# Sch_USBSerie.net
KiCad netlist of a schematic drawn in Altium Designer
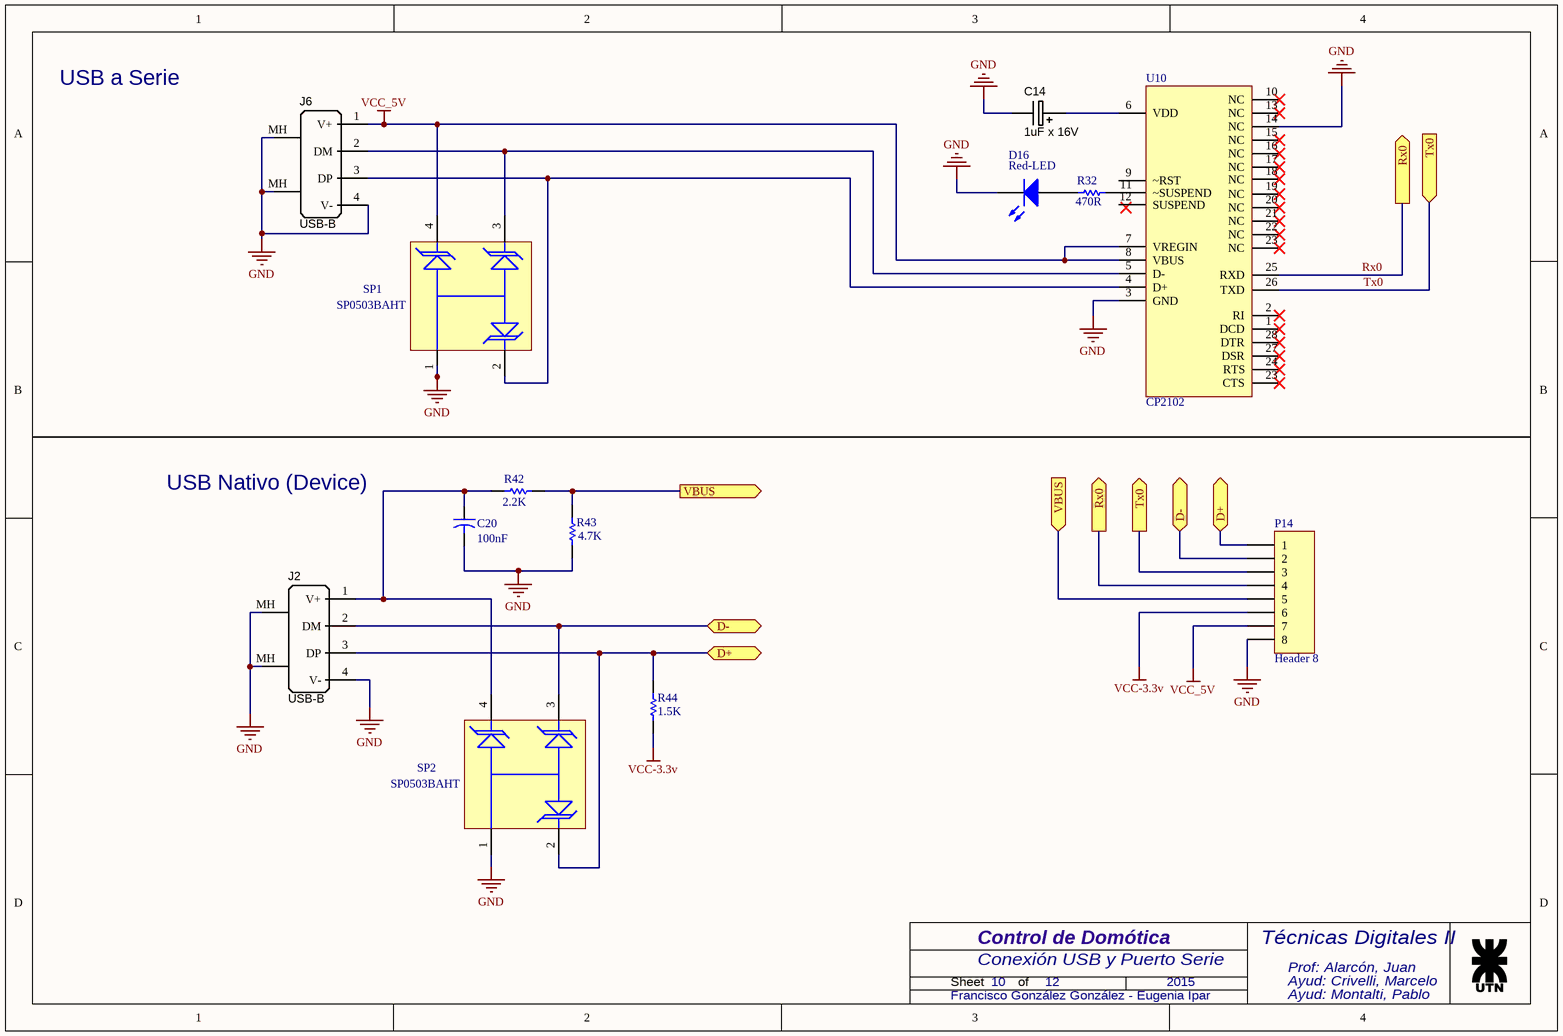
[diagram p0: Sch_USBSerie.SchDoc]

(export (version "E")
  (design (tool "Eeschema 10.0.6"))
  (components
    (comp (ref "C14")
      (value "1uF x 16V")
      (footprint "CAPE3.5mm")
      (description "Capacitor THT Alum Elec 220uF 20% 16V")
      (fields (field (name "TOLERANCE") "±20%"))
      (libsource (lib "PBL - Capacitors") (part "CAPE_220u_16V_THD"))
    )
    (comp (ref "C20")
      (value "100nF")
      (footprint "CAPR5-4X5")
      (description "Capacitor")
      (fields (field (name "Comment") "Cap2") (field (name "PUBLISHER") "Altium Limited"))
      (libsource (lib "Miscellaneous Devices") (part "Cap2"))
    )
    (comp (ref "D16")
      (value "Red-LED")
      (footprint "Type 3mm")
      (description "THT LED round mono-color color lens, WL-TMRW, Super Red")
      (fields (field (name "PARTNUMBER") "151031SS06000") (field (name "MANUFACTURER") "Wuerth Elektronik"))
      (libsource (lib "Altium Content Vault") (part "WE-LED_K1A2-2"))
    )
    (comp (ref "J2")
      (value "USB-B")
      (footprint "USB_TypeB_Tyco")
      (description "Connector THT Type B USB connector")
      (libsource (lib "PBL - Connectors") (part "USB_TypeB"))
    )
    (comp (ref "J6")
      (value "USB-B")
      (footprint "USB_TypeB_Tyco")
      (description "Connector THT Type B USB connector")
      (libsource (lib "PBL - Connectors") (part "USB_TypeB"))
    )
    (comp (ref "P14")
      (value "Header 8")
      (footprint "HDR1X8")
      (description "Header, 8-Pin")
      (fields (field (name "PUBLISHER") "Altium Limited"))
      (libsource (lib "Miscellaneous Connectors") (part "Header 8"))
    )
    (comp (ref "R32")
      (value "470R")
      (footprint "AXIAL-0.3")
      (description "Resistor")
      (fields (field (name "Comment") "Res1") (field (name "PUBLISHER") "Altium Limited"))
      (libsource (lib "Miscellaneous Devices") (part "Res1"))
    )
    (comp (ref "R42")
      (value "2.2K")
      (footprint "AXIAL-0.3")
      (description "Resistor")
      (fields (field (name "Comment") "Res1") (field (name "PUBLISHER") "Altium Limited"))
      (libsource (lib "Miscellaneous Devices") (part "Res1"))
    )
    (comp (ref "R43")
      (value "4.7K")
      (footprint "AXIAL-0.3")
      (description "Resistor")
      (fields (field (name "Comment") "Res1") (field (name "PUBLISHER") "Altium Limited"))
      (libsource (lib "Miscellaneous Devices") (part "Res1"))
    )
    (comp (ref "R44")
      (value "1.5K")
      (footprint "AXIAL-0.3")
      (description "Resistor")
      (fields (field (name "Comment") "Res1") (field (name "PUBLISHER") "Altium Limited"))
      (libsource (lib "Miscellaneous Devices") (part "Res1"))
    )
    (comp (ref "SP1")
      (value "SP0503BAHT")
      (footprint "SOT190P237X120-4N")
      (description "Diode Array 30pF 30kV")
      (libsource (lib "Sch_ArrayDiodo") (part "Component_1"))
    )
    (comp (ref "SP2")
      (value "SP0503BAHT")
      (footprint "SOT190P237X120-4N")
      (description "Diode Array 30pF 30kV")
      (libsource (lib "") (part "Component_1_1"))
    )
    (comp (ref "U10")
      (value "CP2102")
      (footprint "CP2102")
      (libsource (lib "Sch_CP2102") (part "Component_1"))
    )
  )
  (nets
    (net (code "1") (name "/D+") (class "Default")
      (node (ref "J2") (pin "3") (pinfunction "DP_3") (pintype "passive"))
      (node (ref "P14") (pin "1") (pinfunction "1_1") (pintype "passive"))
      (node (ref "R44") (pin "2") (pinfunction "2_2") (pintype "passive"))
      (node (ref "SP2") (pin "2") (pinfunction "2_2") (pintype "passive"))
    )
    (net (code "2") (name "/D-") (class "Default")
      (node (ref "J2") (pin "2") (pinfunction "DM_2") (pintype "passive"))
      (node (ref "P14") (pin "2") (pinfunction "2_2") (pintype "passive"))
      (node (ref "SP2") (pin "3") (pinfunction "3_3") (pintype "passive"))
    )
    (net (code "3") (name "/Rx0") (class "Default")
      (node (ref "P14") (pin "4") (pinfunction "4_4") (pintype "passive"))
      (node (ref "U10") (pin "25") (pinfunction "RXD_25") (pintype "passive"))
    )
    (net (code "4") (name "/Tx0") (class "Default")
      (node (ref "P14") (pin "3") (pinfunction "3_3") (pintype "passive"))
      (node (ref "U10") (pin "26") (pinfunction "TXD_26") (pintype "passive"))
    )
    (net (code "5") (name "/VBUS") (class "Default")
      (node (ref "P14") (pin "5") (pinfunction "5_5") (pintype "passive"))
      (node (ref "R42") (pin "2") (pinfunction "2_2") (pintype "passive"))
      (node (ref "R43") (pin "2") (pinfunction "2_2") (pintype "passive"))
    )
    (net (code "6") (name "GND") (class "Default")
      (node (ref "C14") (pin "2") (pintype "passive"))
      (node (ref "C20") (pin "2") (pinfunction "2_2") (pintype "passive"))
      (node (ref "D16") (pin "1") (pinfunction "K_1") (pintype "passive"))
      (node (ref "J2") (pin "4") (pinfunction "V-_4") (pintype "passive"))
      (node (ref "J2") (pin "MH") (pinfunction "Shell_MH") (pintype "passive"))
      (node (ref "J6") (pin "4") (pinfunction "V-_4") (pintype "passive"))
      (node (ref "J6") (pin "MH") (pinfunction "Shell_MH") (pintype "passive"))
      (node (ref "P14") (pin "8") (pinfunction "8_8") (pintype "passive"))
      (node (ref "R43") (pin "1") (pinfunction "1_1") (pintype "passive"))
      (node (ref "SP1") (pin "1") (pinfunction "1_1") (pintype "passive"))
      (node (ref "SP2") (pin "1") (pinfunction "1_1") (pintype "passive"))
      (node (ref "U10") (pin "14") (pinfunction "NC_14") (pintype "passive"))
      (node (ref "U10") (pin "3") (pinfunction "GND_3") (pintype "passive"))
    )
    (net (code "7") (name "Net-(D16-A)") (class "Default")
      (node (ref "D16") (pin "2") (pinfunction "A_2") (pintype "passive"))
      (node (ref "R32") (pin "1") (pinfunction "1_1") (pintype "passive"))
    )
    (net (code "8") (name "Net-(J2-V+)") (class "Default")
      (node (ref "C20") (pin "1") (pinfunction "1_1") (pintype "passive"))
      (node (ref "J2") (pin "1") (pinfunction "V+_1") (pintype "passive"))
      (node (ref "R42") (pin "1") (pinfunction "1_1") (pintype "passive"))
      (node (ref "SP2") (pin "4") (pinfunction "4_4") (pintype "passive"))
    )
    (net (code "9") (name "Net-(J6-DM)") (class "Default")
      (node (ref "J6") (pin "2") (pinfunction "DM_2") (pintype "passive"))
      (node (ref "SP1") (pin "3") (pinfunction "3_3") (pintype "passive"))
      (node (ref "U10") (pin "5") (pinfunction "D-_5") (pintype "passive"))
    )
    (net (code "10") (name "Net-(J6-DP)") (class "Default")
      (node (ref "J6") (pin "3") (pinfunction "DP_3") (pintype "passive"))
      (node (ref "SP1") (pin "2") (pinfunction "2_2") (pintype "passive"))
      (node (ref "U10") (pin "4") (pinfunction "D+_4") (pintype "passive"))
    )
    (net (code "11") (name "Net-(U10-VDD)") (class "Default")
      (node (ref "C14") (pin "1") (pintype "passive"))
      (node (ref "U10") (pin "6") (pinfunction "VDD_6") (pintype "passive"))
    )
    (net (code "12") (name "Net-(U10-~SUSPEND)") (class "Default")
      (node (ref "R32") (pin "2") (pinfunction "2_2") (pintype "passive"))
      (node (ref "U10") (pin "11") (pinfunction "~SUSPEND_11") (pintype "passive"))
    )
    (net (code "13") (name "VCC-3.3v") (class "Default")
      (node (ref "P14") (pin "6") (pinfunction "6_6") (pintype "passive"))
      (node (ref "R44") (pin "1") (pinfunction "1_1") (pintype "passive"))
    )
    (net (code "14") (name "VCC_5V") (class "Default")
      (node (ref "J6") (pin "1") (pinfunction "V+_1") (pintype "passive"))
      (node (ref "P14") (pin "7") (pinfunction "7_7") (pintype "passive"))
      (node (ref "SP1") (pin "4") (pinfunction "4_4") (pintype "passive"))
      (node (ref "U10") (pin "7") (pinfunction "VREGIN_7") (pintype "passive"))
      (node (ref "U10") (pin "8") (pinfunction "VBUS_8") (pintype "passive"))
    )
    (net (code "15") (name "unconnected-(U10-CTS-Pad23)") (class "Default")
      (node (ref "U10") (pin "23") (pinfunction "CTS_23") (pintype "passive+no_connect"))
    )
    (net (code "16") (name "unconnected-(U10-DCD-Pad1)") (class "Default")
      (node (ref "U10") (pin "1") (pinfunction "DCD_1") (pintype "passive+no_connect"))
    )
    (net (code "17") (name "unconnected-(U10-DSR-Pad27)") (class "Default")
      (node (ref "U10") (pin "27") (pinfunction "DSR_27") (pintype "passive+no_connect"))
    )
    (net (code "18") (name "unconnected-(U10-DTR-Pad28)") (class "Default")
      (node (ref "U10") (pin "28") (pinfunction "DTR_28") (pintype "passive+no_connect"))
    )
    (net (code "19") (name "unconnected-(U10-NC-Pad10)") (class "Default")
      (node (ref "U10") (pin "10") (pinfunction "NC_10") (pintype "passive+no_connect"))
    )
    (net (code "20") (name "unconnected-(U10-NC-Pad13)") (class "Default")
      (node (ref "U10") (pin "13") (pinfunction "NC_13") (pintype "passive+no_connect"))
    )
    (net (code "21") (name "unconnected-(U10-NC-Pad15)") (class "Default")
      (node (ref "U10") (pin "15") (pinfunction "NC_15") (pintype "passive+no_connect"))
    )
    (net (code "22") (name "unconnected-(U10-NC-Pad16)") (class "Default")
      (node (ref "U10") (pin "16") (pinfunction "NC_16") (pintype "passive+no_connect"))
    )
    (net (code "23") (name "unconnected-(U10-NC-Pad17)") (class "Default")
      (node (ref "U10") (pin "17") (pinfunction "NC_17") (pintype "passive+no_connect"))
    )
    (net (code "24") (name "unconnected-(U10-NC-Pad18)") (class "Default")
      (node (ref "U10") (pin "18") (pinfunction "NC_18") (pintype "passive+no_connect"))
    )
    (net (code "25") (name "unconnected-(U10-NC-Pad19)") (class "Default")
      (node (ref "U10") (pin "19") (pinfunction "NC_19") (pintype "passive+no_connect"))
    )
    (net (code "26") (name "unconnected-(U10-NC-Pad20)") (class "Default")
      (node (ref "U10") (pin "20") (pinfunction "NC_20") (pintype "passive+no_connect"))
    )
    (net (code "27") (name "unconnected-(U10-NC-Pad21)") (class "Default")
      (node (ref "U10") (pin "21") (pinfunction "NC_21") (pintype "passive+no_connect"))
    )
    (net (code "28") (name "unconnected-(U10-NC-Pad22)") (class "Default")
      (node (ref "U10") (pin "22") (pinfunction "NC_22") (pintype "passive+no_connect"))
    )
    (net (code "29") (name "unconnected-(U10-NC-Pad23)") (class "Default")
      (node (ref "U10") (pin "23") (pinfunction "NC_23") (pintype "passive+no_connect"))
    )
    (net (code "30") (name "unconnected-(U10-RI-Pad2)") (class "Default")
      (node (ref "U10") (pin "2") (pinfunction "RI_2") (pintype "passive+no_connect"))
    )
    (net (code "31") (name "unconnected-(U10-RTS-Pad24)") (class "Default")
      (node (ref "U10") (pin "24") (pinfunction "RTS_24") (pintype "passive+no_connect"))
    )
    (net (code "32") (name "unconnected-(U10-SUSPEND-Pad12)") (class "Default")
      (node (ref "U10") (pin "12") (pinfunction "SUSPEND_12") (pintype "passive"))
    )
    (net (code "33") (name "unconnected-(U10-~RST-Pad9)") (class "Default")
      (node (ref "U10") (pin "9") (pinfunction "~RST_9") (pintype "passive"))
    )
  )
)
